# House_Illumination.net
KiCad netlist of a schematic drawn in EAGLE
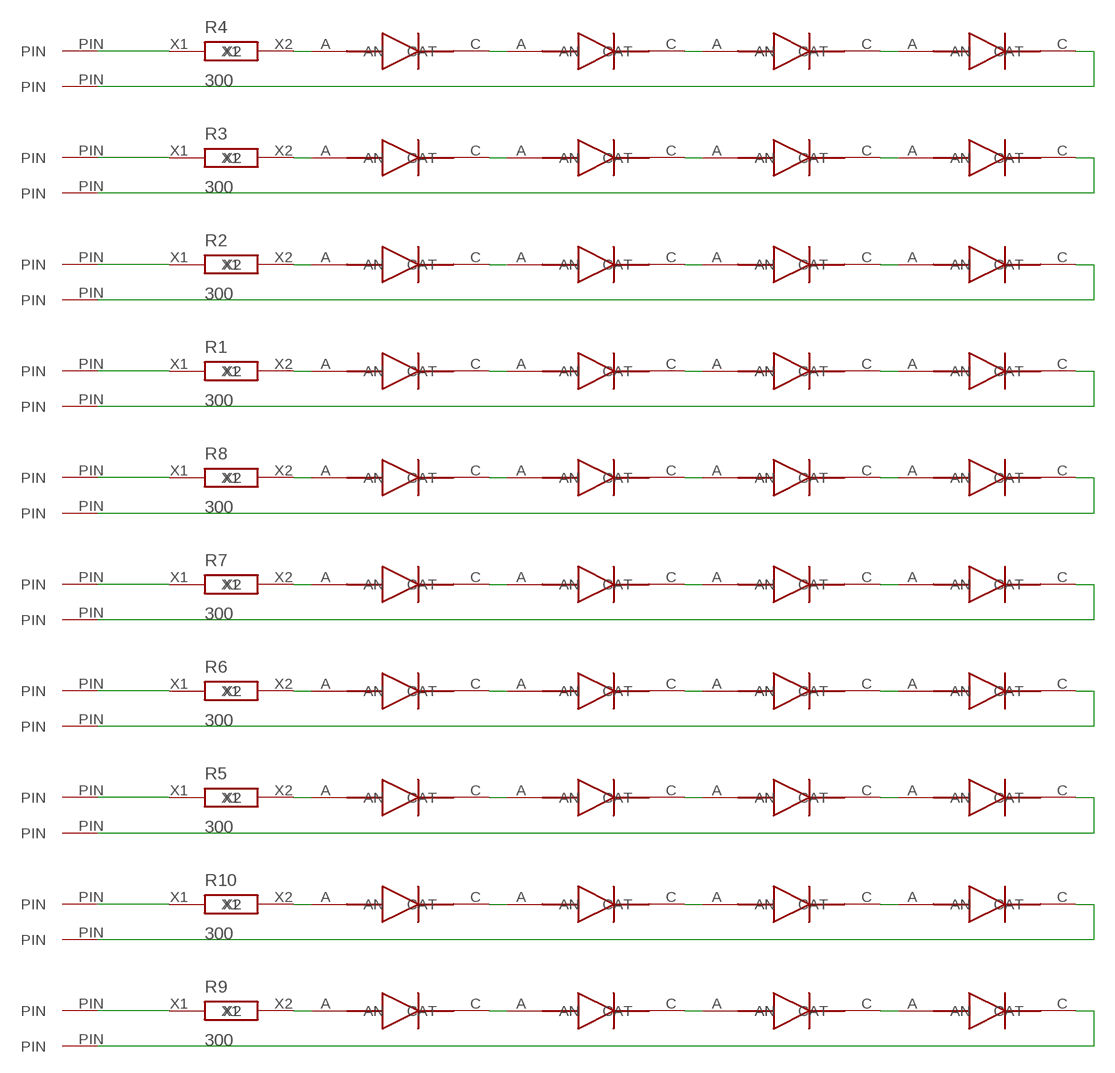
[diagram p0: schematic, sheet 1]

(export (version "E")
  (design (tool "Eeschema 10.0.6"))
  (components
    (comp (ref "R1")
      (value "300")
      (footprint "eagle-import:SMD_2.1X1.25")
      (libsource (lib "eagle-import") (part "R_SMD_2.1X1.25"))
    )
    (comp (ref "R2")
      (value "300")
      (footprint "eagle-import:SMD_2.1X1.25")
      (libsource (lib "eagle-import") (part "R_SMD_2.1X1.25"))
    )
    (comp (ref "R3")
      (value "300")
      (footprint "eagle-import:SMD_2.1X1.25")
      (libsource (lib "eagle-import") (part "R_SMD_2.1X1.25"))
    )
    (comp (ref "R4")
      (value "300")
      (footprint "eagle-import:SMD_2.1X1.25")
      (libsource (lib "eagle-import") (part "R_SMD_2.1X1.25"))
    )
    (comp (ref "R5")
      (value "300")
      (footprint "eagle-import:SMD_2.1X1.25")
      (libsource (lib "eagle-import") (part "R_SMD_2.1X1.25"))
    )
    (comp (ref "R6")
      (value "300")
      (footprint "eagle-import:SMD_2.1X1.25")
      (libsource (lib "eagle-import") (part "R_SMD_2.1X1.25"))
    )
    (comp (ref "R7")
      (value "300")
      (footprint "eagle-import:SMD_2.1X1.25")
      (libsource (lib "eagle-import") (part "R_SMD_2.1X1.25"))
    )
    (comp (ref "R8")
      (value "300")
      (footprint "eagle-import:SMD_2.1X1.25")
      (libsource (lib "eagle-import") (part "R_SMD_2.1X1.25"))
    )
    (comp (ref "R9")
      (value "300")
      (footprint "eagle-import:SMD_2.1X1.25")
      (libsource (lib "eagle-import") (part "R_SMD_2.1X1.25"))
    )
    (comp (ref "R10")
      (value "300")
      (footprint "eagle-import:SMD_2.1X1.25")
      (libsource (lib "eagle-import") (part "R_SMD_2.1X1.25"))
    )
    (comp (ref "U$1")
      (value "PIN_1")
      (footprint "eagle-import:PIN_1")
      (libsource (lib "eagle-import") (part "PIN_1"))
    )
    (comp (ref "U$2")
      (value "PIN_1")
      (footprint "eagle-import:PIN_1")
      (libsource (lib "eagle-import") (part "PIN_1"))
    )
    (comp (ref "U$3")
      (value "LED0805")
      (footprint "eagle-import:LED0805")
      (libsource (lib "eagle-import") (part "LED0805"))
    )
    (comp (ref "U$4")
      (value "LED0805")
      (footprint "eagle-import:LED0805")
      (libsource (lib "eagle-import") (part "LED0805"))
    )
    (comp (ref "U$5")
      (value "LED0805")
      (footprint "eagle-import:LED0805")
      (libsource (lib "eagle-import") (part "LED0805"))
    )
    (comp (ref "U$6")
      (value "LED0805")
      (footprint "eagle-import:LED0805")
      (libsource (lib "eagle-import") (part "LED0805"))
    )
    (comp (ref "U$7")
      (value "PIN_1")
      (footprint "eagle-import:PIN_1")
      (libsource (lib "eagle-import") (part "PIN_1"))
    )
    (comp (ref "U$8")
      (value "PIN_1")
      (footprint "eagle-import:PIN_1")
      (libsource (lib "eagle-import") (part "PIN_1"))
    )
    (comp (ref "U$9")
      (value "LED0805")
      (footprint "eagle-import:LED0805")
      (libsource (lib "eagle-import") (part "LED0805"))
    )
    (comp (ref "U$10")
      (value "LED0805")
      (footprint "eagle-import:LED0805")
      (libsource (lib "eagle-import") (part "LED0805"))
    )
    (comp (ref "U$11")
      (value "LED0805")
      (footprint "eagle-import:LED0805")
      (libsource (lib "eagle-import") (part "LED0805"))
    )
    (comp (ref "U$12")
      (value "LED0805")
      (footprint "eagle-import:LED0805")
      (libsource (lib "eagle-import") (part "LED0805"))
    )
    (comp (ref "U$13")
      (value "PIN_1")
      (footprint "eagle-import:PIN_1")
      (libsource (lib "eagle-import") (part "PIN_1"))
    )
    (comp (ref "U$14")
      (value "PIN_1")
      (footprint "eagle-import:PIN_1")
      (libsource (lib "eagle-import") (part "PIN_1"))
    )
    (comp (ref "U$15")
      (value "LED0805")
      (footprint "eagle-import:LED0805")
      (libsource (lib "eagle-import") (part "LED0805"))
    )
    (comp (ref "U$16")
      (value "LED0805")
      (footprint "eagle-import:LED0805")
      (libsource (lib "eagle-import") (part "LED0805"))
    )
    (comp (ref "U$17")
      (value "LED0805")
      (footprint "eagle-import:LED0805")
      (libsource (lib "eagle-import") (part "LED0805"))
    )
    (comp (ref "U$18")
      (value "LED0805")
      (footprint "eagle-import:LED0805")
      (libsource (lib "eagle-import") (part "LED0805"))
    )
    (comp (ref "U$19")
      (value "PIN_1")
      (footprint "eagle-import:PIN_1")
      (libsource (lib "eagle-import") (part "PIN_1"))
    )
    (comp (ref "U$20")
      (value "PIN_1")
      (footprint "eagle-import:PIN_1")
      (libsource (lib "eagle-import") (part "PIN_1"))
    )
    (comp (ref "U$21")
      (value "LED0805")
      (footprint "eagle-import:LED0805")
      (libsource (lib "eagle-import") (part "LED0805"))
    )
    (comp (ref "U$22")
      (value "LED0805")
      (footprint "eagle-import:LED0805")
      (libsource (lib "eagle-import") (part "LED0805"))
    )
    (comp (ref "U$23")
      (value "LED0805")
      (footprint "eagle-import:LED0805")
      (libsource (lib "eagle-import") (part "LED0805"))
    )
    (comp (ref "U$24")
      (value "LED0805")
      (footprint "eagle-import:LED0805")
      (libsource (lib "eagle-import") (part "LED0805"))
    )
    (comp (ref "U$25")
      (value "PIN_1")
      (footprint "eagle-import:PIN_1")
      (libsource (lib "eagle-import") (part "PIN_1"))
    )
    (comp (ref "U$26")
      (value "PIN_1")
      (footprint "eagle-import:PIN_1")
      (libsource (lib "eagle-import") (part "PIN_1"))
    )
    (comp (ref "U$27")
      (value "LED0805")
      (footprint "eagle-import:LED0805")
      (libsource (lib "eagle-import") (part "LED0805"))
    )
    (comp (ref "U$28")
      (value "LED0805")
      (footprint "eagle-import:LED0805")
      (libsource (lib "eagle-import") (part "LED0805"))
    )
    (comp (ref "U$29")
      (value "LED0805")
      (footprint "eagle-import:LED0805")
      (libsource (lib "eagle-import") (part "LED0805"))
    )
    (comp (ref "U$30")
      (value "LED0805")
      (footprint "eagle-import:LED0805")
      (libsource (lib "eagle-import") (part "LED0805"))
    )
    (comp (ref "U$31")
      (value "PIN_1")
      (footprint "eagle-import:PIN_1")
      (libsource (lib "eagle-import") (part "PIN_1"))
    )
    (comp (ref "U$32")
      (value "PIN_1")
      (footprint "eagle-import:PIN_1")
      (libsource (lib "eagle-import") (part "PIN_1"))
    )
    (comp (ref "U$33")
      (value "LED0805")
      (footprint "eagle-import:LED0805")
      (libsource (lib "eagle-import") (part "LED0805"))
    )
    (comp (ref "U$34")
      (value "LED0805")
      (footprint "eagle-import:LED0805")
      (libsource (lib "eagle-import") (part "LED0805"))
    )
    (comp (ref "U$35")
      (value "LED0805")
      (footprint "eagle-import:LED0805")
      (libsource (lib "eagle-import") (part "LED0805"))
    )
    (comp (ref "U$36")
      (value "LED0805")
      (footprint "eagle-import:LED0805")
      (libsource (lib "eagle-import") (part "LED0805"))
    )
    (comp (ref "U$37")
      (value "PIN_1")
      (footprint "eagle-import:PIN_1")
      (libsource (lib "eagle-import") (part "PIN_1"))
    )
    (comp (ref "U$38")
      (value "PIN_1")
      (footprint "eagle-import:PIN_1")
      (libsource (lib "eagle-import") (part "PIN_1"))
    )
    (comp (ref "U$39")
      (value "LED0805")
      (footprint "eagle-import:LED0805")
      (libsource (lib "eagle-import") (part "LED0805"))
    )
    (comp (ref "U$40")
      (value "LED0805")
      (footprint "eagle-import:LED0805")
      (libsource (lib "eagle-import") (part "LED0805"))
    )
    (comp (ref "U$41")
      (value "LED0805")
      (footprint "eagle-import:LED0805")
      (libsource (lib "eagle-import") (part "LED0805"))
    )
    (comp (ref "U$42")
      (value "LED0805")
      (footprint "eagle-import:LED0805")
      (libsource (lib "eagle-import") (part "LED0805"))
    )
    (comp (ref "U$43")
      (value "PIN_1")
      (footprint "eagle-import:PIN_1")
      (libsource (lib "eagle-import") (part "PIN_1"))
    )
    (comp (ref "U$44")
      (value "PIN_1")
      (footprint "eagle-import:PIN_1")
      (libsource (lib "eagle-import") (part "PIN_1"))
    )
    (comp (ref "U$45")
      (value "LED0805")
      (footprint "eagle-import:LED0805")
      (libsource (lib "eagle-import") (part "LED0805"))
    )
    (comp (ref "U$46")
      (value "LED0805")
      (footprint "eagle-import:LED0805")
      (libsource (lib "eagle-import") (part "LED0805"))
    )
    (comp (ref "U$47")
      (value "LED0805")
      (footprint "eagle-import:LED0805")
      (libsource (lib "eagle-import") (part "LED0805"))
    )
    (comp (ref "U$48")
      (value "LED0805")
      (footprint "eagle-import:LED0805")
      (libsource (lib "eagle-import") (part "LED0805"))
    )
    (comp (ref "U$49")
      (value "PIN_1")
      (footprint "eagle-import:PIN_1")
      (libsource (lib "eagle-import") (part "PIN_1"))
    )
    (comp (ref "U$50")
      (value "PIN_1")
      (footprint "eagle-import:PIN_1")
      (libsource (lib "eagle-import") (part "PIN_1"))
    )
    (comp (ref "U$51")
      (value "LED0805")
      (footprint "eagle-import:LED0805")
      (libsource (lib "eagle-import") (part "LED0805"))
    )
    (comp (ref "U$52")
      (value "LED0805")
      (footprint "eagle-import:LED0805")
      (libsource (lib "eagle-import") (part "LED0805"))
    )
    (comp (ref "U$53")
      (value "LED0805")
      (footprint "eagle-import:LED0805")
      (libsource (lib "eagle-import") (part "LED0805"))
    )
    (comp (ref "U$54")
      (value "LED0805")
      (footprint "eagle-import:LED0805")
      (libsource (lib "eagle-import") (part "LED0805"))
    )
    (comp (ref "U$55")
      (value "PIN_1")
      (footprint "eagle-import:PIN_1")
      (libsource (lib "eagle-import") (part "PIN_1"))
    )
    (comp (ref "U$56")
      (value "PIN_1")
      (footprint "eagle-import:PIN_1")
      (libsource (lib "eagle-import") (part "PIN_1"))
    )
    (comp (ref "U$57")
      (value "LED0805")
      (footprint "eagle-import:LED0805")
      (libsource (lib "eagle-import") (part "LED0805"))
    )
    (comp (ref "U$58")
      (value "LED0805")
      (footprint "eagle-import:LED0805")
      (libsource (lib "eagle-import") (part "LED0805"))
    )
    (comp (ref "U$59")
      (value "LED0805")
      (footprint "eagle-import:LED0805")
      (libsource (lib "eagle-import") (part "LED0805"))
    )
    (comp (ref "U$60")
      (value "LED0805")
      (footprint "eagle-import:LED0805")
      (libsource (lib "eagle-import") (part "LED0805"))
    )
  )
  (nets
    (net (code "1") (name "Net-(R1-PadX1)") (class "Default")
      (node (ref "R1") (pin "X1") (pinfunction "X1_X1") (pintype "bidirectional"))
      (node (ref "U$1") (pin "PIN") (pinfunction "PIN_PIN") (pintype "bidirectional"))
    )
    (net (code "2") (name "Net-(R2-PadX1)") (class "Default")
      (node (ref "R2") (pin "X1") (pinfunction "X1_X1") (pintype "bidirectional"))
      (node (ref "U$7") (pin "PIN") (pinfunction "PIN_PIN") (pintype "bidirectional"))
    )
    (net (code "3") (name "Net-(R3-PadX1)") (class "Default")
      (node (ref "R3") (pin "X1") (pinfunction "X1_X1") (pintype "bidirectional"))
      (node (ref "U$13") (pin "PIN") (pinfunction "PIN_PIN") (pintype "bidirectional"))
    )
    (net (code "4") (name "Net-(R4-PadX1)") (class "Default")
      (node (ref "R4") (pin "X1") (pinfunction "X1_X1") (pintype "bidirectional"))
      (node (ref "U$19") (pin "PIN") (pinfunction "PIN_PIN") (pintype "bidirectional"))
    )
    (net (code "5") (name "Net-(R5-PadX1)") (class "Default")
      (node (ref "R5") (pin "X1") (pinfunction "X1_X1") (pintype "bidirectional"))
      (node (ref "U$25") (pin "PIN") (pinfunction "PIN_PIN") (pintype "bidirectional"))
    )
    (net (code "6") (name "Net-(R6-PadX1)") (class "Default")
      (node (ref "R6") (pin "X1") (pinfunction "X1_X1") (pintype "bidirectional"))
      (node (ref "U$31") (pin "PIN") (pinfunction "PIN_PIN") (pintype "bidirectional"))
    )
    (net (code "7") (name "Net-(R7-PadX1)") (class "Default")
      (node (ref "R7") (pin "X1") (pinfunction "X1_X1") (pintype "bidirectional"))
      (node (ref "U$37") (pin "PIN") (pinfunction "PIN_PIN") (pintype "bidirectional"))
    )
    (net (code "8") (name "Net-(R8-PadX1)") (class "Default")
      (node (ref "R8") (pin "X1") (pinfunction "X1_X1") (pintype "bidirectional"))
      (node (ref "U$43") (pin "PIN") (pinfunction "PIN_PIN") (pintype "bidirectional"))
    )
    (net (code "9") (name "Net-(R9-PadX1)") (class "Default")
      (node (ref "R9") (pin "X1") (pinfunction "X1_X1") (pintype "bidirectional"))
      (node (ref "U$49") (pin "PIN") (pinfunction "PIN_PIN") (pintype "bidirectional"))
    )
    (net (code "10") (name "Net-(R10-PadX1)") (class "Default")
      (node (ref "R10") (pin "X1") (pinfunction "X1_X1") (pintype "bidirectional"))
      (node (ref "U$55") (pin "PIN") (pinfunction "PIN_PIN") (pintype "bidirectional"))
    )
    (net (code "11") (name "Net-(U$3-AN)") (class "Default")
      (node (ref "R1") (pin "X2") (pinfunction "X2_X2") (pintype "bidirectional"))
      (node (ref "U$3") (pin "A") (pinfunction "AN_A") (pintype "bidirectional"))
    )
    (net (code "12") (name "Net-(U$3-CAT)") (class "Default")
      (node (ref "U$3") (pin "C") (pinfunction "CAT_C") (pintype "bidirectional"))
      (node (ref "U$4") (pin "A") (pinfunction "AN_A") (pintype "bidirectional"))
    )
    (net (code "13") (name "Net-(U$4-CAT)") (class "Default")
      (node (ref "U$4") (pin "C") (pinfunction "CAT_C") (pintype "bidirectional"))
      (node (ref "U$5") (pin "A") (pinfunction "AN_A") (pintype "bidirectional"))
    )
    (net (code "14") (name "Net-(U$5-CAT)") (class "Default")
      (node (ref "U$5") (pin "C") (pinfunction "CAT_C") (pintype "bidirectional"))
      (node (ref "U$6") (pin "A") (pinfunction "AN_A") (pintype "bidirectional"))
    )
    (net (code "15") (name "Net-(U$6-CAT)") (class "Default")
      (node (ref "U$2") (pin "PIN") (pinfunction "PIN_PIN") (pintype "bidirectional"))
      (node (ref "U$6") (pin "C") (pinfunction "CAT_C") (pintype "bidirectional"))
    )
    (net (code "16") (name "Net-(U$9-AN)") (class "Default")
      (node (ref "R2") (pin "X2") (pinfunction "X2_X2") (pintype "bidirectional"))
      (node (ref "U$9") (pin "A") (pinfunction "AN_A") (pintype "bidirectional"))
    )
    (net (code "17") (name "Net-(U$10-AN)") (class "Default")
      (node (ref "U$10") (pin "A") (pinfunction "AN_A") (pintype "bidirectional"))
      (node (ref "U$9") (pin "C") (pinfunction "CAT_C") (pintype "bidirectional"))
    )
    (net (code "18") (name "Net-(U$10-CAT)") (class "Default")
      (node (ref "U$10") (pin "C") (pinfunction "CAT_C") (pintype "bidirectional"))
      (node (ref "U$11") (pin "A") (pinfunction "AN_A") (pintype "bidirectional"))
    )
    (net (code "19") (name "Net-(U$11-CAT)") (class "Default")
      (node (ref "U$11") (pin "C") (pinfunction "CAT_C") (pintype "bidirectional"))
      (node (ref "U$12") (pin "A") (pinfunction "AN_A") (pintype "bidirectional"))
    )
    (net (code "20") (name "Net-(U$12-CAT)") (class "Default")
      (node (ref "U$12") (pin "C") (pinfunction "CAT_C") (pintype "bidirectional"))
      (node (ref "U$8") (pin "PIN") (pinfunction "PIN_PIN") (pintype "bidirectional"))
    )
    (net (code "21") (name "Net-(U$15-AN)") (class "Default")
      (node (ref "R3") (pin "X2") (pinfunction "X2_X2") (pintype "bidirectional"))
      (node (ref "U$15") (pin "A") (pinfunction "AN_A") (pintype "bidirectional"))
    )
    (net (code "22") (name "Net-(U$15-CAT)") (class "Default")
      (node (ref "U$15") (pin "C") (pinfunction "CAT_C") (pintype "bidirectional"))
      (node (ref "U$16") (pin "A") (pinfunction "AN_A") (pintype "bidirectional"))
    )
    (net (code "23") (name "Net-(U$16-CAT)") (class "Default")
      (node (ref "U$16") (pin "C") (pinfunction "CAT_C") (pintype "bidirectional"))
      (node (ref "U$17") (pin "A") (pinfunction "AN_A") (pintype "bidirectional"))
    )
    (net (code "24") (name "Net-(U$17-CAT)") (class "Default")
      (node (ref "U$17") (pin "C") (pinfunction "CAT_C") (pintype "bidirectional"))
      (node (ref "U$18") (pin "A") (pinfunction "AN_A") (pintype "bidirectional"))
    )
    (net (code "25") (name "Net-(U$18-CAT)") (class "Default")
      (node (ref "U$14") (pin "PIN") (pinfunction "PIN_PIN") (pintype "bidirectional"))
      (node (ref "U$18") (pin "C") (pinfunction "CAT_C") (pintype "bidirectional"))
    )
    (net (code "26") (name "Net-(U$21-AN)") (class "Default")
      (node (ref "R4") (pin "X2") (pinfunction "X2_X2") (pintype "bidirectional"))
      (node (ref "U$21") (pin "A") (pinfunction "AN_A") (pintype "bidirectional"))
    )
    (net (code "27") (name "Net-(U$21-CAT)") (class "Default")
      (node (ref "U$21") (pin "C") (pinfunction "CAT_C") (pintype "bidirectional"))
      (node (ref "U$22") (pin "A") (pinfunction "AN_A") (pintype "bidirectional"))
    )
    (net (code "28") (name "Net-(U$22-CAT)") (class "Default")
      (node (ref "U$22") (pin "C") (pinfunction "CAT_C") (pintype "bidirectional"))
      (node (ref "U$23") (pin "A") (pinfunction "AN_A") (pintype "bidirectional"))
    )
    (net (code "29") (name "Net-(U$23-CAT)") (class "Default")
      (node (ref "U$23") (pin "C") (pinfunction "CAT_C") (pintype "bidirectional"))
      (node (ref "U$24") (pin "A") (pinfunction "AN_A") (pintype "bidirectional"))
    )
    (net (code "30") (name "Net-(U$24-CAT)") (class "Default")
      (node (ref "U$20") (pin "PIN") (pinfunction "PIN_PIN") (pintype "bidirectional"))
      (node (ref "U$24") (pin "C") (pinfunction "CAT_C") (pintype "bidirectional"))
    )
    (net (code "31") (name "Net-(U$27-AN)") (class "Default")
      (node (ref "R5") (pin "X2") (pinfunction "X2_X2") (pintype "bidirectional"))
      (node (ref "U$27") (pin "A") (pinfunction "AN_A") (pintype "bidirectional"))
    )
    (net (code "32") (name "Net-(U$27-CAT)") (class "Default")
      (node (ref "U$27") (pin "C") (pinfunction "CAT_C") (pintype "bidirectional"))
      (node (ref "U$28") (pin "A") (pinfunction "AN_A") (pintype "bidirectional"))
    )
    (net (code "33") (name "Net-(U$28-CAT)") (class "Default")
      (node (ref "U$28") (pin "C") (pinfunction "CAT_C") (pintype "bidirectional"))
      (node (ref "U$29") (pin "A") (pinfunction "AN_A") (pintype "bidirectional"))
    )
    (net (code "34") (name "Net-(U$29-CAT)") (class "Default")
      (node (ref "U$29") (pin "C") (pinfunction "CAT_C") (pintype "bidirectional"))
      (node (ref "U$30") (pin "A") (pinfunction "AN_A") (pintype "bidirectional"))
    )
    (net (code "35") (name "Net-(U$30-CAT)") (class "Default")
      (node (ref "U$26") (pin "PIN") (pinfunction "PIN_PIN") (pintype "bidirectional"))
      (node (ref "U$30") (pin "C") (pinfunction "CAT_C") (pintype "bidirectional"))
    )
    (net (code "36") (name "Net-(U$33-AN)") (class "Default")
      (node (ref "R6") (pin "X2") (pinfunction "X2_X2") (pintype "bidirectional"))
      (node (ref "U$33") (pin "A") (pinfunction "AN_A") (pintype "bidirectional"))
    )
    (net (code "37") (name "Net-(U$33-CAT)") (class "Default")
      (node (ref "U$33") (pin "C") (pinfunction "CAT_C") (pintype "bidirectional"))
      (node (ref "U$34") (pin "A") (pinfunction "AN_A") (pintype "bidirectional"))
    )
    (net (code "38") (name "Net-(U$34-CAT)") (class "Default")
      (node (ref "U$34") (pin "C") (pinfunction "CAT_C") (pintype "bidirectional"))
      (node (ref "U$35") (pin "A") (pinfunction "AN_A") (pintype "bidirectional"))
    )
    (net (code "39") (name "Net-(U$35-CAT)") (class "Default")
      (node (ref "U$35") (pin "C") (pinfunction "CAT_C") (pintype "bidirectional"))
      (node (ref "U$36") (pin "A") (pinfunction "AN_A") (pintype "bidirectional"))
    )
    (net (code "40") (name "Net-(U$36-CAT)") (class "Default")
      (node (ref "U$32") (pin "PIN") (pinfunction "PIN_PIN") (pintype "bidirectional"))
      (node (ref "U$36") (pin "C") (pinfunction "CAT_C") (pintype "bidirectional"))
    )
    (net (code "41") (name "Net-(U$39-AN)") (class "Default")
      (node (ref "R7") (pin "X2") (pinfunction "X2_X2") (pintype "bidirectional"))
      (node (ref "U$39") (pin "A") (pinfunction "AN_A") (pintype "bidirectional"))
    )
    (net (code "42") (name "Net-(U$39-CAT)") (class "Default")
      (node (ref "U$39") (pin "C") (pinfunction "CAT_C") (pintype "bidirectional"))
      (node (ref "U$40") (pin "A") (pinfunction "AN_A") (pintype "bidirectional"))
    )
    (net (code "43") (name "Net-(U$40-CAT)") (class "Default")
      (node (ref "U$40") (pin "C") (pinfunction "CAT_C") (pintype "bidirectional"))
      (node (ref "U$41") (pin "A") (pinfunction "AN_A") (pintype "bidirectional"))
    )
    (net (code "44") (name "Net-(U$41-CAT)") (class "Default")
      (node (ref "U$41") (pin "C") (pinfunction "CAT_C") (pintype "bidirectional"))
      (node (ref "U$42") (pin "A") (pinfunction "AN_A") (pintype "bidirectional"))
    )
    (net (code "45") (name "Net-(U$42-CAT)") (class "Default")
      (node (ref "U$38") (pin "PIN") (pinfunction "PIN_PIN") (pintype "bidirectional"))
      (node (ref "U$42") (pin "C") (pinfunction "CAT_C") (pintype "bidirectional"))
    )
    (net (code "46") (name "Net-(U$45-AN)") (class "Default")
      (node (ref "R8") (pin "X2") (pinfunction "X2_X2") (pintype "bidirectional"))
      (node (ref "U$45") (pin "A") (pinfunction "AN_A") (pintype "bidirectional"))
    )
    (net (code "47") (name "Net-(U$45-CAT)") (class "Default")
      (node (ref "U$45") (pin "C") (pinfunction "CAT_C") (pintype "bidirectional"))
      (node (ref "U$46") (pin "A") (pinfunction "AN_A") (pintype "bidirectional"))
    )
    (net (code "48") (name "Net-(U$46-CAT)") (class "Default")
      (node (ref "U$46") (pin "C") (pinfunction "CAT_C") (pintype "bidirectional"))
      (node (ref "U$47") (pin "A") (pinfunction "AN_A") (pintype "bidirectional"))
    )
    (net (code "49") (name "Net-(U$47-CAT)") (class "Default")
      (node (ref "U$47") (pin "C") (pinfunction "CAT_C") (pintype "bidirectional"))
      (node (ref "U$48") (pin "A") (pinfunction "AN_A") (pintype "bidirectional"))
    )
    (net (code "50") (name "Net-(U$48-CAT)") (class "Default")
      (node (ref "U$44") (pin "PIN") (pinfunction "PIN_PIN") (pintype "bidirectional"))
      (node (ref "U$48") (pin "C") (pinfunction "CAT_C") (pintype "bidirectional"))
    )
    (net (code "51") (name "Net-(U$51-AN)") (class "Default")
      (node (ref "R9") (pin "X2") (pinfunction "X2_X2") (pintype "bidirectional"))
      (node (ref "U$51") (pin "A") (pinfunction "AN_A") (pintype "bidirectional"))
    )
    (net (code "52") (name "Net-(U$51-CAT)") (class "Default")
      (node (ref "U$51") (pin "C") (pinfunction "CAT_C") (pintype "bidirectional"))
      (node (ref "U$52") (pin "A") (pinfunction "AN_A") (pintype "bidirectional"))
    )
    (net (code "53") (name "Net-(U$52-CAT)") (class "Default")
      (node (ref "U$52") (pin "C") (pinfunction "CAT_C") (pintype "bidirectional"))
      (node (ref "U$53") (pin "A") (pinfunction "AN_A") (pintype "bidirectional"))
    )
    (net (code "54") (name "Net-(U$53-CAT)") (class "Default")
      (node (ref "U$53") (pin "C") (pinfunction "CAT_C") (pintype "bidirectional"))
      (node (ref "U$54") (pin "A") (pinfunction "AN_A") (pintype "bidirectional"))
    )
    (net (code "55") (name "Net-(U$54-CAT)") (class "Default")
      (node (ref "U$50") (pin "PIN") (pinfunction "PIN_PIN") (pintype "bidirectional"))
      (node (ref "U$54") (pin "C") (pinfunction "CAT_C") (pintype "bidirectional"))
    )
    (net (code "56") (name "Net-(U$57-AN)") (class "Default")
      (node (ref "R10") (pin "X2") (pinfunction "X2_X2") (pintype "bidirectional"))
      (node (ref "U$57") (pin "A") (pinfunction "AN_A") (pintype "bidirectional"))
    )
    (net (code "57") (name "Net-(U$57-CAT)") (class "Default")
      (node (ref "U$57") (pin "C") (pinfunction "CAT_C") (pintype "bidirectional"))
      (node (ref "U$58") (pin "A") (pinfunction "AN_A") (pintype "bidirectional"))
    )
    (net (code "58") (name "Net-(U$58-CAT)") (class "Default")
      (node (ref "U$58") (pin "C") (pinfunction "CAT_C") (pintype "bidirectional"))
      (node (ref "U$59") (pin "A") (pinfunction "AN_A") (pintype "bidirectional"))
    )
    (net (code "59") (name "Net-(U$59-CAT)") (class "Default")
      (node (ref "U$59") (pin "C") (pinfunction "CAT_C") (pintype "bidirectional"))
      (node (ref "U$60") (pin "A") (pinfunction "AN_A") (pintype "bidirectional"))
    )
    (net (code "60") (name "Net-(U$60-CAT)") (class "Default")
      (node (ref "U$56") (pin "PIN") (pinfunction "PIN_PIN") (pintype "bidirectional"))
      (node (ref "U$60") (pin "C") (pinfunction "CAT_C") (pintype "bidirectional"))
    )
  )
)
